# tda7418.net
KiCad netlist of a schematic drawn in EAGLE
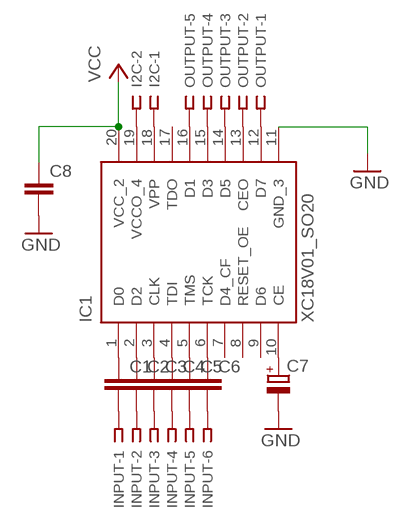
[diagram p0: schematic, sheet 1]

(export (version "E")
  (design (tool "Eeschema 10.0.6"))
  (components
    (comp (ref "C1")
      (value "C5/2.5")
      (footprint "eagle-import:C5B2.5")
      (libsource (lib "eagle-import") (part "C5/2.5"))
    )
    (comp (ref "C2")
      (value "C5/2.5")
      (footprint "eagle-import:C5B2.5")
      (libsource (lib "eagle-import") (part "C5/2.5"))
    )
    (comp (ref "C3")
      (value "C5/2.5")
      (footprint "eagle-import:C5B2.5")
      (libsource (lib "eagle-import") (part "C5/2.5"))
    )
    (comp (ref "C4")
      (value "C5/2.5")
      (footprint "eagle-import:C5B2.5")
      (libsource (lib "eagle-import") (part "C5/2.5"))
    )
    (comp (ref "C5")
      (value "C5/2.5")
      (footprint "eagle-import:C5B2.5")
      (libsource (lib "eagle-import") (part "C5/2.5"))
    )
    (comp (ref "C6")
      (value "C5/2.5")
      (footprint "eagle-import:C5B2.5")
      (libsource (lib "eagle-import") (part "C5/2.5"))
    )
    (comp (ref "C7")
      (value "CPOL-EUE5-4")
      (footprint "eagle-import:E5-4")
      (libsource (lib "eagle-import") (part "CPOL-EUE5-4"))
    )
    (comp (ref "C8")
      (value "C-EU050-035X075")
      (footprint "eagle-import:C050-035X075")
      (libsource (lib "eagle-import") (part "C-EU050-035X075"))
    )
    (comp (ref "I2C")
      (value "SSW-102-02-S-S")
      (footprint "eagle-import:SSW-102-02-S-S")
      (libsource (lib "eagle-import") (part "SSW-102-02-S-S"))
    )
    (comp (ref "IC1")
      (value "XC18V01_SO20")
      (footprint "eagle-import:SOP20")
      (libsource (lib "eagle-import") (part "XC18V01_SO20"))
    )
    (comp (ref "INPUT")
      (value "SSW-106-02-S-S")
      (footprint "eagle-import:SSW-106-02-S-S")
      (libsource (lib "eagle-import") (part "SSW-106-02-S-S"))
    )
    (comp (ref "OUTPUT")
      (value "SSW-105-02-S-S")
      (footprint "eagle-import:SSW-105-02-S-S")
      (libsource (lib "eagle-import") (part "SSW-105-02-S-S"))
    )
  )
  (nets
    (net (code "1") (name "GND") (class "Default")
      (node (ref "C7") (pin "-") (pinfunction "-_-") (pintype "passive"))
      (node (ref "C8") (pin "2") (pinfunction "2_2") (pintype "passive"))
      (node (ref "IC1") (pin "11") (pinfunction "GND_3_11") (pintype "passive"))
    )
    (net (code "2") (name "Net-(C1-Pad2)") (class "Default")
      (node (ref "C1") (pin "2") (pinfunction "2_2") (pintype "passive"))
      (node (ref "INPUT") (pin "1") (pinfunction "1_1") (pintype "passive"))
    )
    (net (code "3") (name "Net-(I2CB-1)") (class "Default")
      (node (ref "I2C") (pin "2") (pinfunction "1_2") (pintype "passive"))
      (node (ref "IC1") (pin "19") (pinfunction "VCCO_4_19") (pintype "passive"))
    )
    (net (code "4") (name "Net-(IC1-CE)") (class "Default")
      (node (ref "C7") (pin "+") (pinfunction "+_+") (pintype "passive"))
      (node (ref "IC1") (pin "10") (pinfunction "CE_10") (pintype "input"))
    )
    (net (code "5") (name "Net-(IC1-CEO)") (class "Default")
      (node (ref "IC1") (pin "13") (pinfunction "CEO_13") (pintype "output"))
      (node (ref "OUTPUT") (pin "2") (pinfunction "1_2") (pintype "passive"))
    )
    (net (code "6") (name "Net-(IC1-CLK)") (class "Default")
      (node (ref "C3") (pin "1") (pinfunction "1_1") (pintype "passive"))
      (node (ref "IC1") (pin "3") (pinfunction "CLK_3") (pintype "input"))
    )
    (net (code "7") (name "Net-(IC1-D0)") (class "Default")
      (node (ref "C1") (pin "1") (pinfunction "1_1") (pintype "passive"))
      (node (ref "IC1") (pin "1") (pinfunction "D0_1") (pintype "output"))
    )
    (net (code "8") (name "Net-(IC1-D1)") (class "Default")
      (node (ref "IC1") (pin "16") (pinfunction "D1_16") (pintype "output"))
      (node (ref "OUTPUT") (pin "5") (pinfunction "1_5") (pintype "passive"))
    )
    (net (code "9") (name "Net-(IC1-D2)") (class "Default")
      (node (ref "C2") (pin "1") (pinfunction "1_1") (pintype "passive"))
      (node (ref "IC1") (pin "2") (pinfunction "D2_2") (pintype "output"))
    )
    (net (code "10") (name "Net-(IC1-D3)") (class "Default")
      (node (ref "IC1") (pin "15") (pinfunction "D3_15") (pintype "output"))
      (node (ref "OUTPUT") (pin "4") (pinfunction "1_4") (pintype "passive"))
    )
    (net (code "11") (name "Net-(IC1-D5)") (class "Default")
      (node (ref "IC1") (pin "14") (pinfunction "D5_14") (pintype "output"))
      (node (ref "OUTPUT") (pin "3") (pinfunction "1_3") (pintype "passive"))
    )
    (net (code "12") (name "Net-(IC1-D7)") (class "Default")
      (node (ref "IC1") (pin "12") (pinfunction "D7_12") (pintype "output"))
      (node (ref "OUTPUT") (pin "1") (pinfunction "1_1") (pintype "passive"))
    )
    (net (code "13") (name "Net-(IC1-TCK)") (class "Default")
      (node (ref "C6") (pin "1") (pinfunction "1_1") (pintype "passive"))
      (node (ref "IC1") (pin "6") (pinfunction "TCK_6") (pintype "input"))
    )
    (net (code "14") (name "Net-(IC1-TDI)") (class "Default")
      (node (ref "C4") (pin "1") (pinfunction "1_1") (pintype "passive"))
      (node (ref "IC1") (pin "4") (pinfunction "TDI_4") (pintype "input"))
    )
    (net (code "15") (name "Net-(IC1-TMS)") (class "Default")
      (node (ref "C5") (pin "1") (pinfunction "1_1") (pintype "passive"))
      (node (ref "IC1") (pin "5") (pinfunction "TMS_5") (pintype "input"))
    )
    (net (code "16") (name "Net-(IC1-VPP)") (class "Default")
      (node (ref "I2C") (pin "1") (pinfunction "1_1") (pintype "passive"))
      (node (ref "IC1") (pin "18") (pinfunction "VPP_18") (pintype "passive"))
    )
    (net (code "17") (name "Net-(INPUTB-1)") (class "Default")
      (node (ref "C2") (pin "2") (pinfunction "2_2") (pintype "passive"))
      (node (ref "INPUT") (pin "2") (pinfunction "1_2") (pintype "passive"))
    )
    (net (code "18") (name "Net-(INPUTC-1)") (class "Default")
      (node (ref "C3") (pin "2") (pinfunction "2_2") (pintype "passive"))
      (node (ref "INPUT") (pin "3") (pinfunction "1_3") (pintype "passive"))
    )
    (net (code "19") (name "Net-(INPUTD-1)") (class "Default")
      (node (ref "C4") (pin "2") (pinfunction "2_2") (pintype "passive"))
      (node (ref "INPUT") (pin "4") (pinfunction "1_4") (pintype "passive"))
    )
    (net (code "20") (name "Net-(INPUTE-1)") (class "Default")
      (node (ref "C5") (pin "2") (pinfunction "2_2") (pintype "passive"))
      (node (ref "INPUT") (pin "5") (pinfunction "1_5") (pintype "passive"))
    )
    (net (code "21") (name "Net-(INPUTF-1)") (class "Default")
      (node (ref "C6") (pin "2") (pinfunction "2_2") (pintype "passive"))
      (node (ref "INPUT") (pin "6") (pinfunction "1_6") (pintype "passive"))
    )
    (net (code "22") (name "VCC") (class "Default")
      (node (ref "C8") (pin "1") (pinfunction "1_1") (pintype "passive"))
      (node (ref "IC1") (pin "20") (pinfunction "VCC_2_20") (pintype "passive"))
    )
    (net (code "23") (name "unconnected-(IC1-D4_CF-Pad7)") (class "Default")
      (node (ref "IC1") (pin "7") (pinfunction "D4_CF_7") (pintype "output"))
    )
    (net (code "24") (name "unconnected-(IC1-D6-Pad9)") (class "Default")
      (node (ref "IC1") (pin "9") (pinfunction "D6_9") (pintype "output"))
    )
    (net (code "25") (name "unconnected-(IC1-RESET_OE-Pad8)") (class "Default")
      (node (ref "IC1") (pin "8") (pinfunction "RESET_OE_8") (pintype "bidirectional"))
    )
    (net (code "26") (name "unconnected-(IC1-TDO-Pad17)") (class "Default")
      (node (ref "IC1") (pin "17") (pinfunction "TDO_17") (pintype "output"))
    )
  )
)
